# 6WP_arduino_DFPlayer.net
KiCad netlist of a schematic drawn in EAGLE
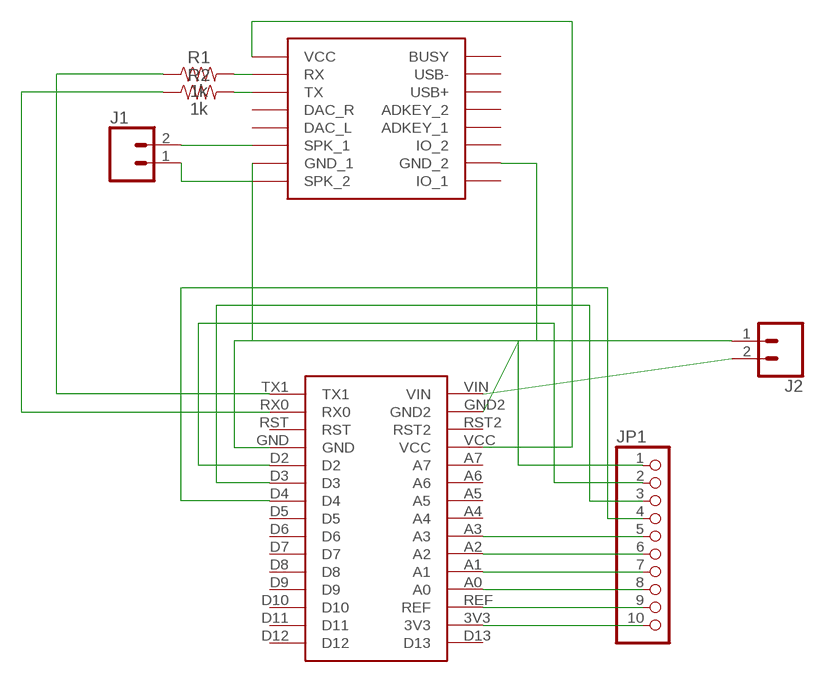
[diagram p0: schematic, sheet 1]

(export (version "E")
  (design (tool "Eeschema 10.0.6"))
  (components
    (comp (ref "A3")
      (value "ARDUINONANO")
      (footprint "eagle-import:ARDUINONANO")
      (libsource (lib "eagle-import") (part "ARDUINONANO"))
    )
    (comp (ref "J1")
      (value "CONN_02JST-PTH-2")
      (footprint "eagle-import:JST-2-PTH")
      (libsource (lib "eagle-import") (part "CONN_02JST-PTH-2"))
    )
    (comp (ref "J2")
      (value "CONN_02JST-PTH-2")
      (footprint "eagle-import:JST-2-PTH")
      (libsource (lib "eagle-import") (part "CONN_02JST-PTH-2"))
    )
    (comp (ref "JP1")
      (value "PINHD-1X10/90")
      (footprint "eagle-import:1X10_90")
      (libsource (lib "eagle-import") (part "PINHD-1X10/90"))
    )
    (comp (ref "R1")
      (value "1k")
      (footprint "eagle-import:AXIAL-0.3")
      (libsource (lib "eagle-import") (part "1KOHM-HORIZ-1/4W-1%"))
    )
    (comp (ref "R2")
      (value "1k")
      (footprint "eagle-import:AXIAL-0.3")
      (libsource (lib "eagle-import") (part "1KOHM-HORIZ-1/4W-1%"))
    )
    (comp (ref "U$1")
      (value "DFPLAYER")
      (footprint "eagle-import:DFPLAYER")
      (libsource (lib "eagle-import") (part "DFPLAYER"))
    )
  )
  (nets
    (net (code "1") (name "Net-(A3-Pad3V3)") (class "Default")
      (node (ref "A3") (pin "3V3") (pinfunction "3V3_3V3") (pintype "bidirectional"))
      (node (ref "JP1") (pin "10") (pinfunction "10_10") (pintype "passive"))
    )
    (net (code "2") (name "Net-(A3-PadA0)") (class "Default")
      (node (ref "A3") (pin "A0") (pinfunction "A0_A0") (pintype "bidirectional"))
      (node (ref "JP1") (pin "8") (pinfunction "8_8") (pintype "passive"))
    )
    (net (code "3") (name "Net-(A3-PadA1)") (class "Default")
      (node (ref "A3") (pin "A1") (pinfunction "A1_A1") (pintype "bidirectional"))
      (node (ref "JP1") (pin "7") (pinfunction "7_7") (pintype "passive"))
    )
    (net (code "4") (name "Net-(A3-PadA2)") (class "Default")
      (node (ref "A3") (pin "A2") (pinfunction "A2_A2") (pintype "bidirectional"))
      (node (ref "JP1") (pin "6") (pinfunction "6_6") (pintype "passive"))
    )
    (net (code "5") (name "Net-(A3-PadA3)") (class "Default")
      (node (ref "A3") (pin "A3") (pinfunction "A3_A3") (pintype "bidirectional"))
      (node (ref "JP1") (pin "5") (pinfunction "5_5") (pintype "passive"))
    )
    (net (code "6") (name "Net-(A3-PadD2)") (class "Default")
      (node (ref "A3") (pin "D2") (pinfunction "D2_D2") (pintype "bidirectional"))
      (node (ref "JP1") (pin "2") (pinfunction "2_2") (pintype "passive"))
    )
    (net (code "7") (name "Net-(A3-PadD3)") (class "Default")
      (node (ref "A3") (pin "D3") (pinfunction "D3_D3") (pintype "bidirectional"))
      (node (ref "JP1") (pin "3") (pinfunction "3_3") (pintype "passive"))
    )
    (net (code "8") (name "Net-(A3-PadD4)") (class "Default")
      (node (ref "A3") (pin "D4") (pinfunction "D4_D4") (pintype "bidirectional"))
      (node (ref "JP1") (pin "4") (pinfunction "4_4") (pintype "passive"))
    )
    (net (code "9") (name "Net-(A3-PadGND)") (class "Default")
      (node (ref "A3") (pin "GND") (pinfunction "GND_GND") (pintype "bidirectional"))
      (node (ref "A3") (pin "GND2") (pinfunction "GND2_GND2") (pintype "bidirectional"))
      (node (ref "J2") (pin "1") (pinfunction "1_1") (pintype "passive"))
      (node (ref "JP1") (pin "1") (pinfunction "1_1") (pintype "passive"))
      (node (ref "U$1") (pin "GND_1") (pinfunction "GND_1_GND_1") (pintype "bidirectional"))
      (node (ref "U$1") (pin "GND_2") (pinfunction "GND_2_GND_2") (pintype "bidirectional"))
    )
    (net (code "10") (name "Net-(A3-PadREF)") (class "Default")
      (node (ref "A3") (pin "REF") (pinfunction "REF_REF") (pintype "bidirectional"))
      (node (ref "JP1") (pin "9") (pinfunction "9_9") (pintype "passive"))
    )
    (net (code "11") (name "Net-(A3-PadVCC)") (class "Default")
      (node (ref "A3") (pin "VCC") (pinfunction "VCC_VCC") (pintype "bidirectional"))
      (node (ref "U$1") (pin "VCC") (pinfunction "VCC_VCC") (pintype "bidirectional"))
    )
    (net (code "12") (name "Net-(A3-PadVIN)") (class "Default")
      (node (ref "A3") (pin "VIN") (pinfunction "VIN_VIN") (pintype "bidirectional"))
      (node (ref "J2") (pin "2") (pinfunction "2_2") (pintype "passive"))
    )
    (net (code "13") (name "Net-(R1-1)") (class "Default")
      (node (ref "A3") (pin "TX1") (pinfunction "TX1_TX1") (pintype "bidirectional"))
      (node (ref "R1") (pin "P$1") (pinfunction "1_P$1") (pintype "passive"))
    )
    (net (code "14") (name "Net-(R1-2)") (class "Default")
      (node (ref "R1") (pin "P$2") (pinfunction "2_P$2") (pintype "passive"))
      (node (ref "U$1") (pin "RX") (pinfunction "RX_RX") (pintype "bidirectional"))
    )
    (net (code "15") (name "Net-(R2-1)") (class "Default")
      (node (ref "A3") (pin "RX0") (pinfunction "RX0_RX0") (pintype "bidirectional"))
      (node (ref "R2") (pin "P$1") (pinfunction "1_P$1") (pintype "passive"))
    )
    (net (code "16") (name "Net-(R2-2)") (class "Default")
      (node (ref "R2") (pin "P$2") (pinfunction "2_P$2") (pintype "passive"))
      (node (ref "U$1") (pin "TX") (pinfunction "TX_TX") (pintype "bidirectional"))
    )
    (net (code "17") (name "Net-(U$1-SPK_1)") (class "Default")
      (node (ref "J1") (pin "2") (pinfunction "2_2") (pintype "passive"))
      (node (ref "U$1") (pin "SPK1") (pinfunction "SPK_1_SPK1") (pintype "bidirectional"))
    )
    (net (code "18") (name "Net-(U$1-SPK_2)") (class "Default")
      (node (ref "J1") (pin "1") (pinfunction "1_1") (pintype "passive"))
      (node (ref "U$1") (pin "SPK2") (pinfunction "SPK_2_SPK2") (pintype "bidirectional"))
    )
    (net (code "19") (name "unconnected-(A3-PadA4)") (class "Default")
      (node (ref "A3") (pin "A4") (pinfunction "A4_A4") (pintype "bidirectional"))
    )
    (net (code "20") (name "unconnected-(A3-PadA5)") (class "Default")
      (node (ref "A3") (pin "A5") (pinfunction "A5_A5") (pintype "bidirectional"))
    )
    (net (code "21") (name "unconnected-(A3-PadA6)") (class "Default")
      (node (ref "A3") (pin "A6") (pinfunction "A6_A6") (pintype "bidirectional"))
    )
    (net (code "22") (name "unconnected-(A3-PadA7)") (class "Default")
      (node (ref "A3") (pin "A7") (pinfunction "A7_A7") (pintype "bidirectional"))
    )
    (net (code "23") (name "unconnected-(A3-PadD5)") (class "Default")
      (node (ref "A3") (pin "D5") (pinfunction "D5_D5") (pintype "bidirectional"))
    )
    (net (code "24") (name "unconnected-(A3-PadD6)") (class "Default")
      (node (ref "A3") (pin "D6") (pinfunction "D6_D6") (pintype "bidirectional"))
    )
    (net (code "25") (name "unconnected-(A3-PadD7)") (class "Default")
      (node (ref "A3") (pin "D7") (pinfunction "D7_D7") (pintype "bidirectional"))
    )
    (net (code "26") (name "unconnected-(A3-PadD8)") (class "Default")
      (node (ref "A3") (pin "D8") (pinfunction "D8_D8") (pintype "bidirectional"))
    )
    (net (code "27") (name "unconnected-(A3-PadD9)") (class "Default")
      (node (ref "A3") (pin "D9") (pinfunction "D9_D9") (pintype "bidirectional"))
    )
    (net (code "28") (name "unconnected-(A3-PadD10)") (class "Default")
      (node (ref "A3") (pin "D10") (pinfunction "D10_D10") (pintype "bidirectional"))
    )
    (net (code "29") (name "unconnected-(A3-PadD11)") (class "Default")
      (node (ref "A3") (pin "D11") (pinfunction "D11_D11") (pintype "bidirectional"))
    )
    (net (code "30") (name "unconnected-(A3-PadD12)") (class "Default")
      (node (ref "A3") (pin "D12") (pinfunction "D12_D12") (pintype "bidirectional"))
    )
    (net (code "31") (name "unconnected-(A3-PadD13)") (class "Default")
      (node (ref "A3") (pin "D13") (pinfunction "D13_D13") (pintype "bidirectional"))
    )
    (net (code "32") (name "unconnected-(A3-PadRST)") (class "Default")
      (node (ref "A3") (pin "RST") (pinfunction "RST_RST") (pintype "bidirectional"))
    )
    (net (code "33") (name "unconnected-(A3-PadRST2)") (class "Default")
      (node (ref "A3") (pin "RST2") (pinfunction "RST2_RST2") (pintype "bidirectional"))
    )
    (net (code "34") (name "unconnected-(U$1-ADKEY_1-PadADKEY1)") (class "Default")
      (node (ref "U$1") (pin "ADKEY1") (pinfunction "ADKEY_1_ADKEY1") (pintype "bidirectional"))
    )
    (net (code "35") (name "unconnected-(U$1-ADKEY_2-PadADKEY2)") (class "Default")
      (node (ref "U$1") (pin "ADKEY2") (pinfunction "ADKEY_2_ADKEY2") (pintype "bidirectional"))
    )
    (net (code "36") (name "unconnected-(U$1-IO_1-PadIO1)") (class "Default")
      (node (ref "U$1") (pin "IO1") (pinfunction "IO_1_IO1") (pintype "bidirectional"))
    )
    (net (code "37") (name "unconnected-(U$1-IO_2-PadIO2)") (class "Default")
      (node (ref "U$1") (pin "IO2") (pinfunction "IO_2_IO2") (pintype "bidirectional"))
    )
    (net (code "38") (name "unconnected-(U$1-PadBUSY)") (class "Default")
      (node (ref "U$1") (pin "BUSY") (pinfunction "BUSY_BUSY") (pintype "bidirectional"))
    )
    (net (code "39") (name "unconnected-(U$1-PadDAC_L)") (class "Default")
      (node (ref "U$1") (pin "DAC_L") (pinfunction "DAC_L_DAC_L") (pintype "bidirectional"))
    )
    (net (code "40") (name "unconnected-(U$1-PadDAC_R)") (class "Default")
      (node (ref "U$1") (pin "DAC_R") (pinfunction "DAC_R_DAC_R") (pintype "bidirectional"))
    )
    (net (code "41") (name "unconnected-(U$1-PadUSB+)") (class "Default")
      (node (ref "U$1") (pin "USB+") (pinfunction "USB+_USB+") (pintype "bidirectional"))
    )
    (net (code "42") (name "unconnected-(U$1-PadUSB-)") (class "Default")
      (node (ref "U$1") (pin "USB-") (pinfunction "USB-_USB-") (pintype "bidirectional"))
    )
  )
)
